# power_led_v4.net
KiCad netlist of a schematic drawn in EAGLE
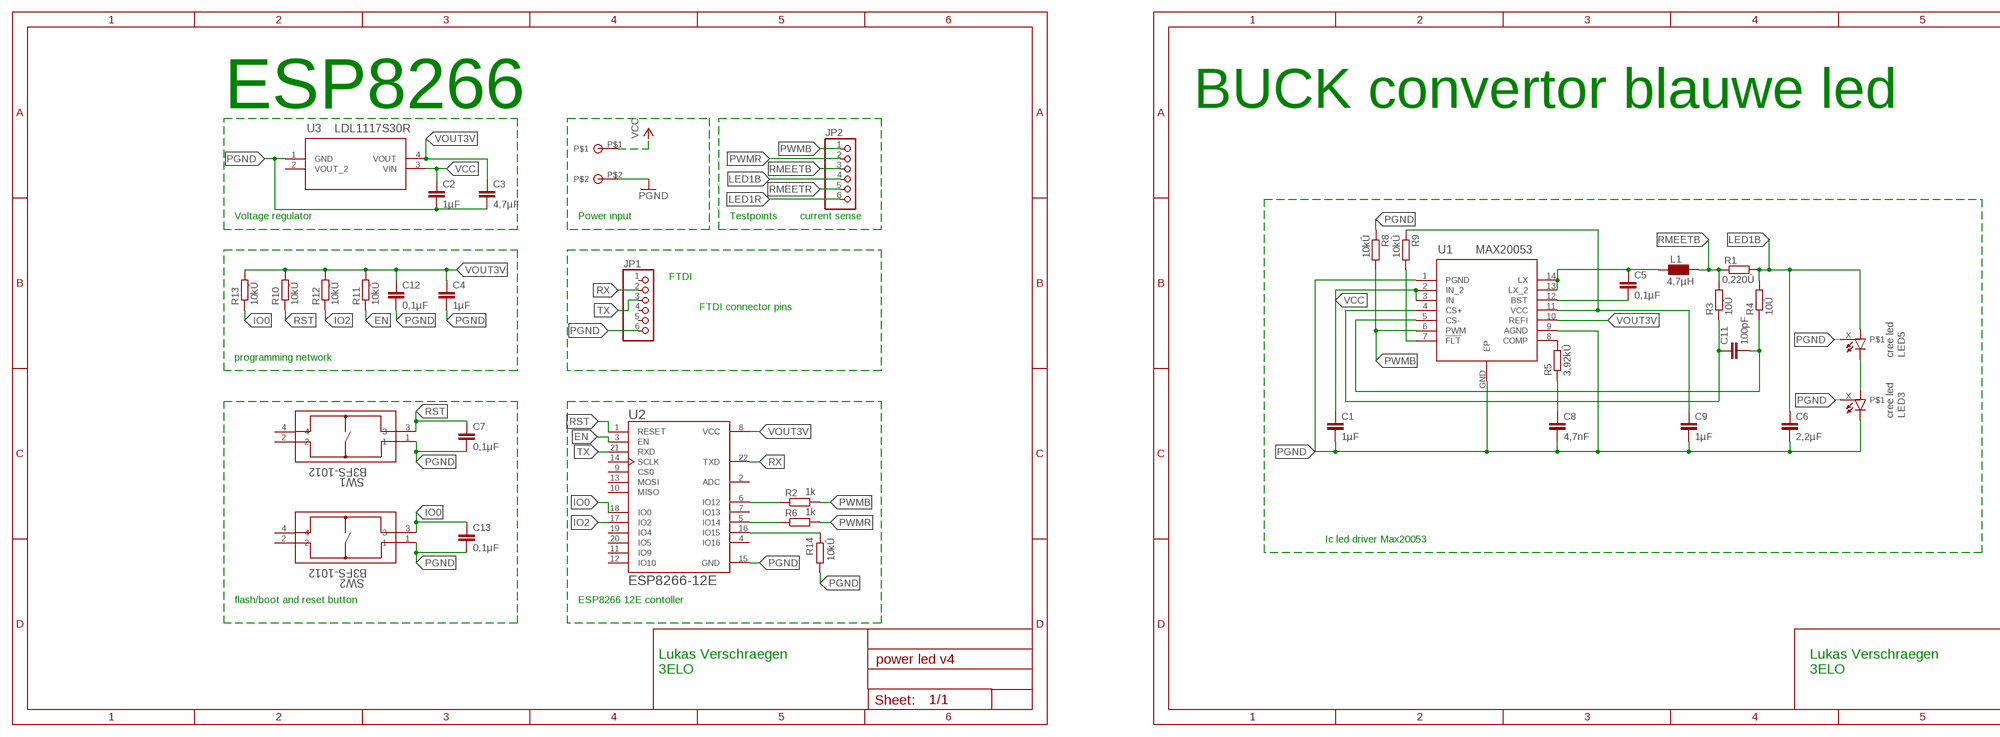
[diagram p0: schematic, sheet 1, part 1 of 2]
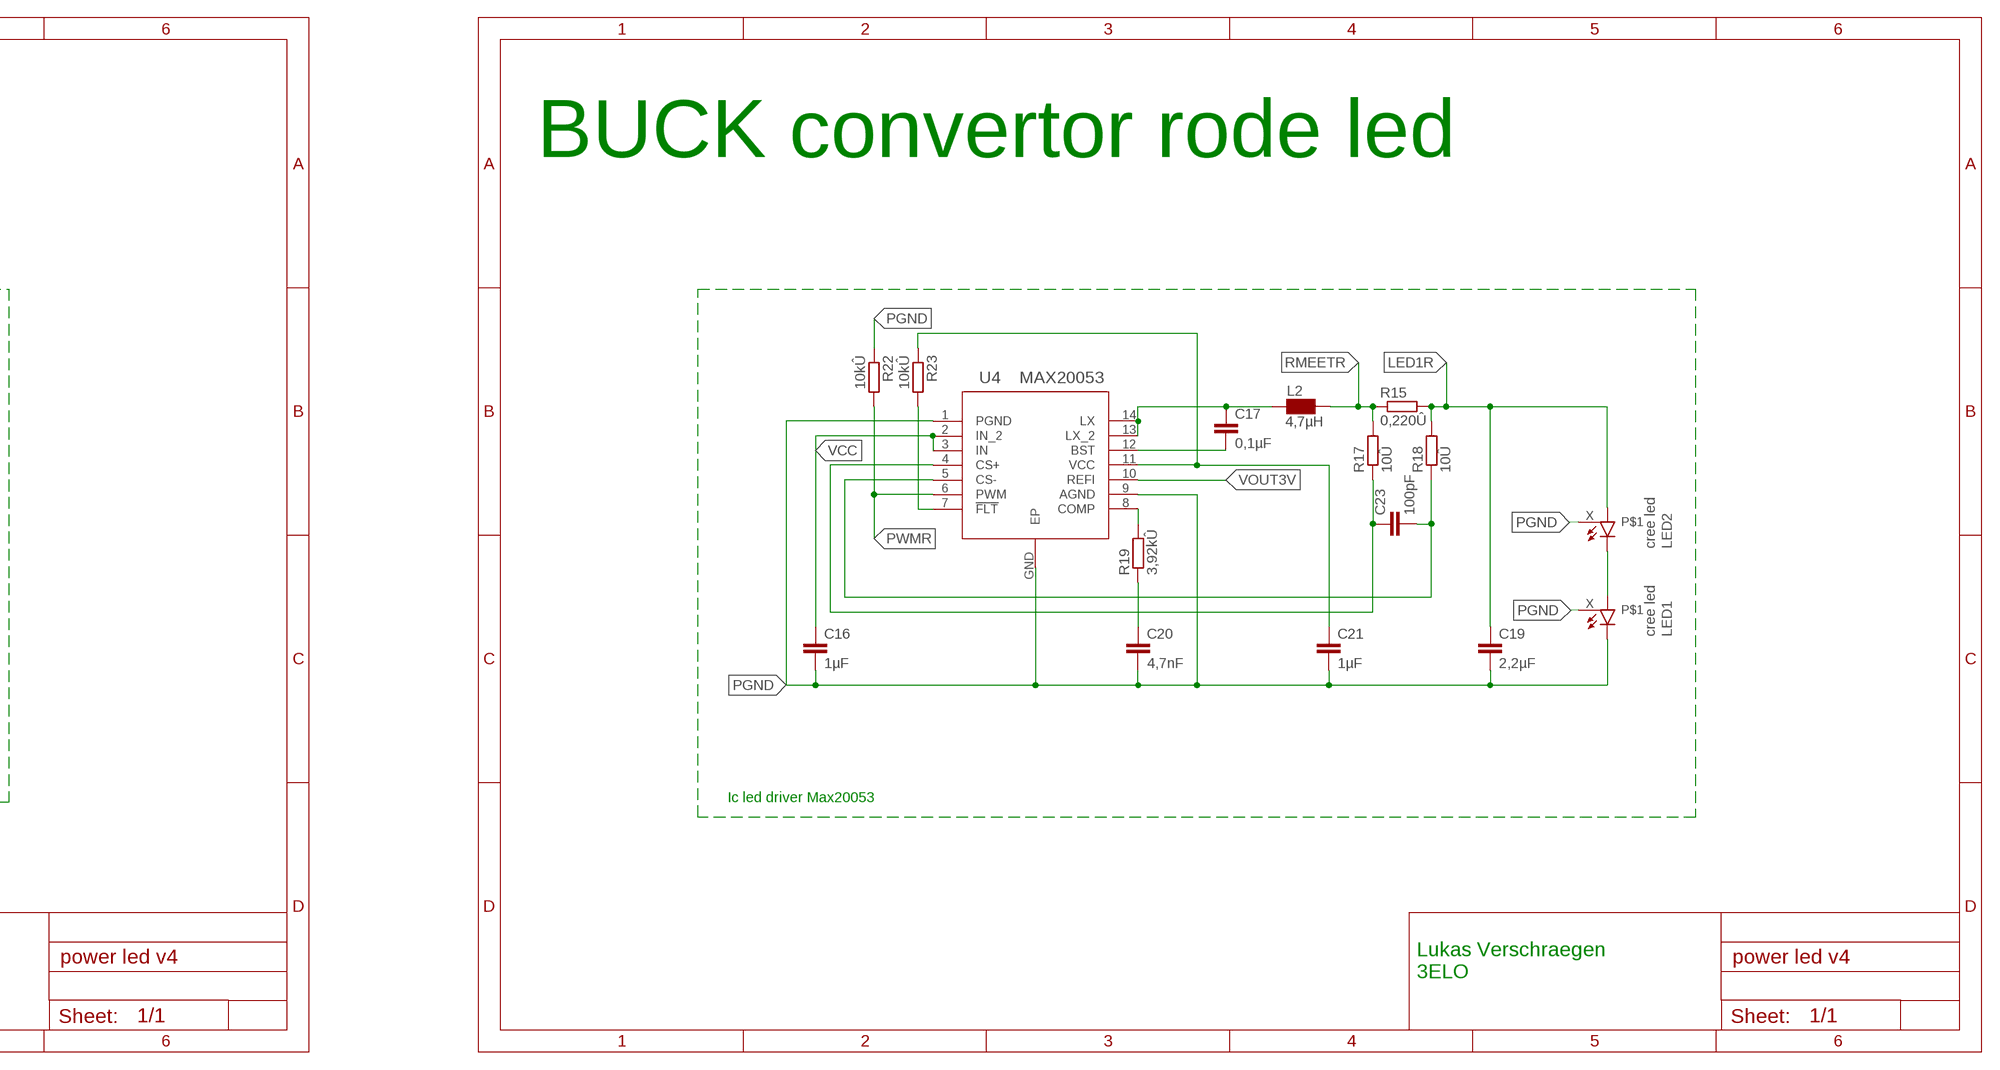
[diagram p1: schematic, sheet 1, part 2 of 2]

(export (version "E")
  (design (tool "Eeschema 10.0.6"))
  (components
    (comp (ref "C1")
      (value "1µF")
      (footprint "eagle-import:C1206")
      (libsource (lib "eagle-import") (part "C-EUC1206"))
    )
    (comp (ref "C2")
      (value "1µF")
      (footprint "eagle-import:C1206")
      (libsource (lib "eagle-import") (part "C-EUC1206"))
    )
    (comp (ref "C3")
      (value "4,7µF")
      (footprint "eagle-import:C1206")
      (libsource (lib "eagle-import") (part "C-EUC1206"))
    )
    (comp (ref "C4")
      (value "1µF")
      (footprint "eagle-import:C1206")
      (libsource (lib "eagle-import") (part "C-EUC1206"))
    )
    (comp (ref "C5")
      (value "0,1µF")
      (footprint "eagle-import:C1206")
      (libsource (lib "eagle-import") (part "C-EUC1206"))
    )
    (comp (ref "C6")
      (value "2,2µF")
      (footprint "eagle-import:C1206")
      (libsource (lib "eagle-import") (part "C-EUC1206"))
    )
    (comp (ref "C7")
      (value "0,1µF")
      (footprint "eagle-import:C1206")
      (libsource (lib "eagle-import") (part "C-EUC1206"))
    )
    (comp (ref "C8")
      (value "4,7nF")
      (footprint "eagle-import:C1206")
      (libsource (lib "eagle-import") (part "C-EUC1206"))
    )
    (comp (ref "C9")
      (value "1µF")
      (footprint "eagle-import:C1206")
      (libsource (lib "eagle-import") (part "C-EUC1206"))
    )
    (comp (ref "C11")
      (value "100pF")
      (footprint "eagle-import:C1206")
      (libsource (lib "eagle-import") (part "C-EUC1206"))
    )
    (comp (ref "C12")
      (value "0,1µF")
      (footprint "eagle-import:C1206")
      (libsource (lib "eagle-import") (part "C-EUC1206"))
    )
    (comp (ref "C13")
      (value "0,1µF")
      (footprint "eagle-import:C1206")
      (libsource (lib "eagle-import") (part "C-EUC1206"))
    )
    (comp (ref "C16")
      (value "1µF")
      (footprint "eagle-import:C1206")
      (libsource (lib "eagle-import") (part "C-EUC1206"))
    )
    (comp (ref "C17")
      (value "0,1µF")
      (footprint "eagle-import:C1206")
      (libsource (lib "eagle-import") (part "C-EUC1206"))
    )
    (comp (ref "C19")
      (value "2,2µF")
      (footprint "eagle-import:C1206")
      (libsource (lib "eagle-import") (part "C-EUC1206"))
    )
    (comp (ref "C20")
      (value "4,7nF")
      (footprint "eagle-import:C1206")
      (libsource (lib "eagle-import") (part "C-EUC1206"))
    )
    (comp (ref "C21")
      (value "1µF")
      (footprint "eagle-import:C1206")
      (libsource (lib "eagle-import") (part "C-EUC1206"))
    )
    (comp (ref "C23")
      (value "100pF")
      (footprint "eagle-import:C1206")
      (libsource (lib "eagle-import") (part "C-EUC1206"))
    )
    (comp (ref "JP1")
      (value "PINHD-1X6")
      (footprint "eagle-import:1X06")
      (libsource (lib "eagle-import") (part "PINHD-1X6"))
    )
    (comp (ref "JP2")
      (value "PINHD-1X6")
      (footprint "eagle-import:1X06")
      (libsource (lib "eagle-import") (part "PINHD-1X6"))
    )
    (comp (ref "L1")
      (value "4,7µH")
      (footprint "eagle-import:IND_7447789004_WRE-M")
      (fields
        (field (name "MANUFACTURER_PART_NUMBER") "7447789004")
        (field (name "COPYRIGHT") "Copyright (C) 2022 Ultra Librarian. All rights reserved.")
      )
      (libsource (lib "eagle-import") (part "7447789004IND_7447789004_WRE-M"))
    )
    (comp (ref "L2")
      (value "4,7µH")
      (footprint "eagle-import:IND_7447789004_WRE-M")
      (fields
        (field (name "MANUFACTURER_PART_NUMBER") "7447789004")
        (field (name "COPYRIGHT") "Copyright (C) 2022 Ultra Librarian. All rights reserved.")
      )
      (libsource (lib "eagle-import") (part "7447789004IND_7447789004_WRE-M"))
    )
    (comp (ref "LED1")
      (value "cree led")
      (footprint "eagle-import:CREE_XLAMP")
      (libsource (lib "eagle-import") (part "XPEWHT-01-0000-00BC2"))
    )
    (comp (ref "LED2")
      (value "cree led")
      (footprint "eagle-import:CREE_XLAMP")
      (libsource (lib "eagle-import") (part "XPEWHT-01-0000-00BC2"))
    )
    (comp (ref "LED3")
      (value "cree led")
      (footprint "eagle-import:CREE_XLAMP")
      (libsource (lib "eagle-import") (part "XPEWHT-01-0000-00BC2"))
    )
    (comp (ref "LED5")
      (value "cree led")
      (footprint "eagle-import:CREE_XLAMP")
      (libsource (lib "eagle-import") (part "XPEWHT-01-0000-00BC2"))
    )
    (comp (ref "R1")
      (value "0,220Û")
      (footprint "eagle-import:R1206")
      (libsource (lib "eagle-import") (part "R-EU_R1206"))
    )
    (comp (ref "R2")
      (value "1k")
      (footprint "eagle-import:R1206")
      (libsource (lib "eagle-import") (part "R-EU_R1206"))
    )
    (comp (ref "R3")
      (value "10Û")
      (footprint "eagle-import:R1206")
      (libsource (lib "eagle-import") (part "R-EU_R1206"))
    )
    (comp (ref "R4")
      (value "10Û")
      (footprint "eagle-import:R1206")
      (libsource (lib "eagle-import") (part "R-EU_R1206"))
    )
    (comp (ref "R5")
      (value "3,92kÛ")
      (footprint "eagle-import:R1206")
      (libsource (lib "eagle-import") (part "R-EU_R1206"))
    )
    (comp (ref "R6")
      (value "1k")
      (footprint "eagle-import:R1206")
      (libsource (lib "eagle-import") (part "R-EU_R1206"))
    )
    (comp (ref "R8")
      (value "10kÛ")
      (footprint "eagle-import:R1206")
      (libsource (lib "eagle-import") (part "R-EU_R1206"))
    )
    (comp (ref "R9")
      (value "10kÛ")
      (footprint "eagle-import:R1206")
      (libsource (lib "eagle-import") (part "R-EU_R1206"))
    )
    (comp (ref "R10")
      (value "10kÛ")
      (footprint "eagle-import:R1206")
      (libsource (lib "eagle-import") (part "R-EU_R1206"))
    )
    (comp (ref "R11")
      (value "10kÛ")
      (footprint "eagle-import:R1206")
      (libsource (lib "eagle-import") (part "R-EU_R1206"))
    )
    (comp (ref "R12")
      (value "10kÛ")
      (footprint "eagle-import:R1206")
      (libsource (lib "eagle-import") (part "R-EU_R1206"))
    )
    (comp (ref "R13")
      (value "10kÛ")
      (footprint "eagle-import:R1206")
      (libsource (lib "eagle-import") (part "R-EU_R1206"))
    )
    (comp (ref "R14")
      (value "10kÛ")
      (footprint "eagle-import:R1206")
      (libsource (lib "eagle-import") (part "R-EU_R1206"))
    )
    (comp (ref "R15")
      (value "0,220Û")
      (footprint "eagle-import:R1206")
      (libsource (lib "eagle-import") (part "R-EU_R1206"))
    )
    (comp (ref "R17")
      (value "10Û")
      (footprint "eagle-import:R1206")
      (libsource (lib "eagle-import") (part "R-EU_R1206"))
    )
    (comp (ref "R18")
      (value "10Û")
      (footprint "eagle-import:R1206")
      (libsource (lib "eagle-import") (part "R-EU_R1206"))
    )
    (comp (ref "R19")
      (value "3,92kÛ")
      (footprint "eagle-import:R1206")
      (libsource (lib "eagle-import") (part "R-EU_R1206"))
    )
    (comp (ref "R22")
      (value "10kÛ")
      (footprint "eagle-import:R1206")
      (libsource (lib "eagle-import") (part "R-EU_R1206"))
    )
    (comp (ref "R23")
      (value "10kÛ")
      (footprint "eagle-import:R1206")
      (libsource (lib "eagle-import") (part "R-EU_R1206"))
    )
    (comp (ref "SW1")
      (value "B3FS-1012")
      (footprint "eagle-import:SW_B3FS-1010_OMR")
      (fields (field (name "COPYRIGHT") "Copyright (C) 2018 Accelerated Designs. All rights reserved"))
      (libsource (lib "eagle-import") (part "B3FS-1012"))
    )
    (comp (ref "SW2")
      (value "B3FS-1012")
      (footprint "eagle-import:SW_B3FS-1010_OMR")
      (fields (field (name "COPYRIGHT") "Copyright (C) 2018 Accelerated Designs. All rights reserved"))
      (libsource (lib "eagle-import") (part "B3FS-1012"))
    )
    (comp (ref "U1")
      (value "MAX20053")
      (footprint "eagle-import:21-0108-E_14L_MXM-M")
      (fields
        (field (name "MANUFACTURER_PART_NUMBER") "MAX20053AUD/V+")
        (field (name "COPYRIGHT") "Copyright (C) 2022 Ultra Librarian. All rights reserved.")
      )
      (libsource (lib "eagle-import") (part "MAX20053AUD/V+21-0108-E_14L_MXM-M"))
    )
    (comp (ref "U2")
      (value "ESP8266-12E")
      (footprint "eagle-import:XCVR_ESP8266-12E_ESP-12E")
      (fields (field (name "MF") "AI-Thinker") (field (name "MP") "ESP8266-12E/ESP-12E"))
      (libsource (lib "eagle-import") (part "ESP8266-12E/ESP-12E"))
    )
    (comp (ref "U3")
      (value "LDL1117S30R")
      (footprint "eagle-import:SOT223_STM")
      (fields (field (name "COPYRIGHT") "Copyright (C) 2022 Ultra Librarian. All rights reserved."))
      (libsource (lib "eagle-import") (part "LDL1117S30R"))
    )
    (comp (ref "U4")
      (value "MAX20053")
      (footprint "eagle-import:21-0108-E_14L_MXM-M")
      (fields
        (field (name "MANUFACTURER_PART_NUMBER") "MAX20053AUD/V+")
        (field (name "COPYRIGHT") "Copyright (C) 2022 Ultra Librarian. All rights reserved.")
      )
      (libsource (lib "eagle-import") (part "MAX20053AUD/V+21-0108-E_14L_MXM-M"))
    )
    (comp (ref "X1")
      (value "TERMINA5MM")
      (footprint "eagle-import:TERMINAL5MM")
      (libsource (lib "eagle-import") (part "TERMINA5MM"))
    )
  )
  (nets
    (net (code "1") (name "EN") (class "Default")
      (node (ref "R11") (pin "1") (pinfunction "1_1") (pintype "passive"))
      (node (ref "U2") (pin "3") (pinfunction "EN_3") (pintype "input"))
    )
    (net (code "2") (name "IO0") (class "Default")
      (node (ref "C13") (pin "1") (pinfunction "1_1") (pintype "passive"))
      (node (ref "R13") (pin "1") (pinfunction "1_1") (pintype "passive"))
      (node (ref "SW2") (pin "3") (pinfunction "3_3") (pintype "passive"))
      (node (ref "U2") (pin "18") (pinfunction "IO0_18") (pintype "bidirectional"))
    )
    (net (code "3") (name "IO2") (class "Default")
      (node (ref "R12") (pin "1") (pinfunction "1_1") (pintype "passive"))
      (node (ref "U2") (pin "17") (pinfunction "IO2_17") (pintype "bidirectional"))
    )
    (net (code "4") (name "LED1B") (class "Default")
      (node (ref "C6") (pin "1") (pinfunction "1_1") (pintype "passive"))
      (node (ref "JP2") (pin "4") (pinfunction "4_4") (pintype "passive"))
      (node (ref "LED5") (pin "A") (pinfunction "A_A") (pintype "passive"))
      (node (ref "LED5") (pin "A@1") (pinfunction "A_A@1") (pintype "passive"))
      (node (ref "R1") (pin "2") (pinfunction "2_2") (pintype "passive"))
      (node (ref "R4") (pin "2") (pinfunction "2_2") (pintype "passive"))
    )
    (net (code "5") (name "LED1R") (class "Default")
      (node (ref "C19") (pin "1") (pinfunction "1_1") (pintype "passive"))
      (node (ref "JP2") (pin "6") (pinfunction "6_6") (pintype "passive"))
      (node (ref "LED2") (pin "A") (pinfunction "A_A") (pintype "passive"))
      (node (ref "LED2") (pin "A@1") (pinfunction "A_A@1") (pintype "passive"))
      (node (ref "R15") (pin "2") (pinfunction "2_2") (pintype "passive"))
      (node (ref "R18") (pin "2") (pinfunction "2_2") (pintype "passive"))
    )
    (net (code "6") (name "Net-(C8-Pad1)") (class "Default")
      (node (ref "C8") (pin "1") (pinfunction "1_1") (pintype "passive"))
      (node (ref "R5") (pin "1") (pinfunction "1_1") (pintype "passive"))
    )
    (net (code "7") (name "Net-(C20-Pad1)") (class "Default")
      (node (ref "C20") (pin "1") (pinfunction "1_1") (pintype "passive"))
      (node (ref "R19") (pin "1") (pinfunction "1_1") (pintype "passive"))
    )
    (net (code "8") (name "Net-(LED1-A-PadA@1)") (class "Default")
      (node (ref "LED1") (pin "A") (pinfunction "A_A") (pintype "passive"))
      (node (ref "LED1") (pin "A@1") (pinfunction "A_A@1") (pintype "passive"))
      (node (ref "LED2") (pin "C") (pinfunction "C_C") (pintype "passive"))
      (node (ref "LED2") (pin "C@1") (pinfunction "C_C@1") (pintype "passive"))
    )
    (net (code "9") (name "Net-(LED3-A-PadA@1)") (class "Default")
      (node (ref "LED3") (pin "A") (pinfunction "A_A") (pintype "passive"))
      (node (ref "LED3") (pin "A@1") (pinfunction "A_A@1") (pintype "passive"))
      (node (ref "LED5") (pin "C") (pinfunction "C_C") (pintype "passive"))
      (node (ref "LED5") (pin "C@1") (pinfunction "C_C@1") (pintype "passive"))
    )
    (net (code "10") (name "Net-(U1-BST)") (class "Default")
      (node (ref "C5") (pin "2") (pinfunction "2_2") (pintype "passive"))
      (node (ref "U1") (pin "12") (pinfunction "BST_12") (pintype "passive"))
    )
    (net (code "11") (name "Net-(U1-COMP)") (class "Default")
      (node (ref "R5") (pin "2") (pinfunction "2_2") (pintype "passive"))
      (node (ref "U1") (pin "8") (pinfunction "COMP_8") (pintype "output"))
    )
    (net (code "12") (name "Net-(U1-CS+)") (class "Default")
      (node (ref "C11") (pin "1") (pinfunction "1_1") (pintype "passive"))
      (node (ref "R3") (pin "1") (pinfunction "1_1") (pintype "passive"))
      (node (ref "U1") (pin "4") (pinfunction "CS+_4") (pintype "input"))
    )
    (net (code "13") (name "Net-(U1-CS-)") (class "Default")
      (node (ref "C11") (pin "2") (pinfunction "2_2") (pintype "passive"))
      (node (ref "R4") (pin "1") (pinfunction "1_1") (pintype "passive"))
      (node (ref "U1") (pin "5") (pinfunction "CS-_5") (pintype "input"))
    )
    (net (code "14") (name "Net-(U1-LX)") (class "Default")
      (node (ref "C5") (pin "1") (pinfunction "1_1") (pintype "passive"))
      (node (ref "L1") (pin "2") (pinfunction "2_2") (pintype "passive"))
      (node (ref "U1") (pin "13") (pinfunction "LX_2_13") (pintype "output"))
      (node (ref "U1") (pin "14") (pinfunction "LX_14") (pintype "output"))
    )
    (net (code "15") (name "Net-(U1-VCC)") (class "Default")
      (node (ref "C9") (pin "1") (pinfunction "1_1") (pintype "passive"))
      (node (ref "R9") (pin "1") (pinfunction "1_1") (pintype "passive"))
      (node (ref "U1") (pin "11") (pinfunction "VCC_11") (pintype "power_in"))
    )
    (net (code "16") (name "Net-(U1-~{FLT})") (class "Default")
      (node (ref "R9") (pin "2") (pinfunction "2_2") (pintype "passive"))
      (node (ref "U1") (pin "7") (pinfunction "~{FLT}_7") (pintype "output"))
    )
    (net (code "17") (name "Net-(U2-IO12)") (class "Default")
      (node (ref "R2") (pin "1") (pinfunction "1_1") (pintype "passive"))
      (node (ref "U2") (pin "6") (pinfunction "IO12_6") (pintype "bidirectional"))
    )
    (net (code "18") (name "Net-(U2-IO14)") (class "Default")
      (node (ref "R6") (pin "1") (pinfunction "1_1") (pintype "passive"))
      (node (ref "U2") (pin "5") (pinfunction "IO14_5") (pintype "bidirectional"))
    )
    (net (code "19") (name "Net-(U2-IO15)") (class "Default")
      (node (ref "R14") (pin "1") (pinfunction "1_1") (pintype "passive"))
      (node (ref "U2") (pin "16") (pinfunction "IO15_16") (pintype "bidirectional"))
    )
    (net (code "20") (name "Net-(U4-BST)") (class "Default")
      (node (ref "C17") (pin "2") (pinfunction "2_2") (pintype "passive"))
      (node (ref "U4") (pin "12") (pinfunction "BST_12") (pintype "passive"))
    )
    (net (code "21") (name "Net-(U4-COMP)") (class "Default")
      (node (ref "R19") (pin "2") (pinfunction "2_2") (pintype "passive"))
      (node (ref "U4") (pin "8") (pinfunction "COMP_8") (pintype "output"))
    )
    (net (code "22") (name "Net-(U4-CS+)") (class "Default")
      (node (ref "C23") (pin "1") (pinfunction "1_1") (pintype "passive"))
      (node (ref "R17") (pin "1") (pinfunction "1_1") (pintype "passive"))
      (node (ref "U4") (pin "4") (pinfunction "CS+_4") (pintype "input"))
    )
    (net (code "23") (name "Net-(U4-CS-)") (class "Default")
      (node (ref "C23") (pin "2") (pinfunction "2_2") (pintype "passive"))
      (node (ref "R18") (pin "1") (pinfunction "1_1") (pintype "passive"))
      (node (ref "U4") (pin "5") (pinfunction "CS-_5") (pintype "input"))
    )
    (net (code "24") (name "Net-(U4-LX)") (class "Default")
      (node (ref "C17") (pin "1") (pinfunction "1_1") (pintype "passive"))
      (node (ref "L2") (pin "2") (pinfunction "2_2") (pintype "passive"))
      (node (ref "U4") (pin "13") (pinfunction "LX_2_13") (pintype "output"))
      (node (ref "U4") (pin "14") (pinfunction "LX_14") (pintype "output"))
    )
    (net (code "25") (name "Net-(U4-VCC)") (class "Default")
      (node (ref "C21") (pin "1") (pinfunction "1_1") (pintype "passive"))
      (node (ref "R23") (pin "1") (pinfunction "1_1") (pintype "passive"))
      (node (ref "U4") (pin "11") (pinfunction "VCC_11") (pintype "power_in"))
    )
    (net (code "26") (name "Net-(U4-~{FLT})") (class "Default")
      (node (ref "R23") (pin "2") (pinfunction "2_2") (pintype "passive"))
      (node (ref "U4") (pin "7") (pinfunction "~{FLT}_7") (pintype "output"))
    )
    (net (code "27") (name "PGND") (class "Default")
      (node (ref "C1") (pin "2") (pinfunction "2_2") (pintype "passive"))
      (node (ref "C12") (pin "2") (pinfunction "2_2") (pintype "passive"))
      (node (ref "C13") (pin "2") (pinfunction "2_2") (pintype "passive"))
      (node (ref "C16") (pin "2") (pinfunction "2_2") (pintype "passive"))
      (node (ref "C19") (pin "2") (pinfunction "2_2") (pintype "passive"))
      (node (ref "C2") (pin "2") (pinfunction "2_2") (pintype "passive"))
      (node (ref "C20") (pin "2") (pinfunction "2_2") (pintype "passive"))
      (node (ref "C21") (pin "2") (pinfunction "2_2") (pintype "passive"))
      (node (ref "C3") (pin "2") (pinfunction "2_2") (pintype "passive"))
      (node (ref "C4") (pin "2") (pinfunction "2_2") (pintype "passive"))
      (node (ref "C6") (pin "2") (pinfunction "2_2") (pintype "passive"))
      (node (ref "C7") (pin "2") (pinfunction "2_2") (pintype "passive"))
      (node (ref "C8") (pin "2") (pinfunction "2_2") (pintype "passive"))
      (node (ref "C9") (pin "2") (pinfunction "2_2") (pintype "passive"))
      (node (ref "JP1") (pin "6") (pinfunction "6_6") (pintype "passive"))
      (node (ref "LED1") (pin "C") (pinfunction "C_C") (pintype "passive"))
      (node (ref "LED1") (pin "C@1") (pinfunction "C_C@1") (pintype "passive"))
      (node (ref "LED1") (pin "X") (pinfunction "P$1_X") (pintype "bidirectional"))
      (node (ref "LED2") (pin "X") (pinfunction "P$1_X") (pintype "bidirectional"))
      (node (ref "LED3") (pin "C") (pinfunction "C_C") (pintype "passive"))
      (node (ref "LED3") (pin "C@1") (pinfunction "C_C@1") (pintype "passive"))
      (node (ref "LED3") (pin "X") (pinfunction "P$1_X") (pintype "bidirectional"))
      (node (ref "LED5") (pin "X") (pinfunction "P$1_X") (pintype "bidirectional"))
      (node (ref "R14") (pin "2") (pinfunction "2_2") (pintype "passive"))
      (node (ref "R22") (pin "1") (pinfunction "1_1") (pintype "passive"))
      (node (ref "R8") (pin "1") (pinfunction "1_1") (pintype "passive"))
      (node (ref "SW1") (pin "1") (pinfunction "1_1") (pintype "passive"))
      (node (ref "SW2") (pin "1") (pinfunction "1_1") (pintype "passive"))
      (node (ref "U1") (pin "1") (pinfunction "PGND_1") (pintype "power_in"))
      (node (ref "U1") (pin "9") (pinfunction "AGND_9") (pintype "power_in"))
      (node (ref "U1") (pin "GND") (pinfunction "EP_GND") (pintype "bidirectional"))
      (node (ref "U2") (pin "15") (pinfunction "GND_15") (pintype "power_in"))
      (node (ref "U3") (pin "1") (pinfunction "GND_1") (pintype "passive"))
      (node (ref "U4") (pin "1") (pinfunction "PGND_1") (pintype "power_in"))
      (node (ref "U4") (pin "9") (pinfunction "AGND_9") (pintype "power_in"))
      (node (ref "U4") (pin "GND") (pinfunction "EP_GND") (pintype "bidirectional"))
      (node (ref "X1") (pin "P$2") (pinfunction "P$2_P$2") (pintype "input"))
    )
    (net (code "28") (name "PWMB") (class "Default")
      (node (ref "JP2") (pin "1") (pinfunction "1_1") (pintype "passive"))
      (node (ref "R2") (pin "2") (pinfunction "2_2") (pintype "passive"))
      (node (ref "R8") (pin "2") (pinfunction "2_2") (pintype "passive"))
      (node (ref "U1") (pin "6") (pinfunction "PWM_6") (pintype "input"))
    )
    (net (code "29") (name "PWMR") (class "Default")
      (node (ref "JP2") (pin "2") (pinfunction "2_2") (pintype "passive"))
      (node (ref "R22") (pin "2") (pinfunction "2_2") (pintype "passive"))
      (node (ref "R6") (pin "2") (pinfunction "2_2") (pintype "passive"))
      (node (ref "U4") (pin "6") (pinfunction "PWM_6") (pintype "input"))
    )
    (net (code "30") (name "RMEETB") (class "Default")
      (node (ref "JP2") (pin "3") (pinfunction "3_3") (pintype "passive"))
      (node (ref "L1") (pin "1") (pinfunction "1_1") (pintype "passive"))
      (node (ref "R1") (pin "1") (pinfunction "1_1") (pintype "passive"))
      (node (ref "R3") (pin "2") (pinfunction "2_2") (pintype "passive"))
    )
    (net (code "31") (name "RMEETR") (class "Default")
      (node (ref "JP2") (pin "5") (pinfunction "5_5") (pintype "passive"))
      (node (ref "L2") (pin "1") (pinfunction "1_1") (pintype "passive"))
      (node (ref "R15") (pin "1") (pinfunction "1_1") (pintype "passive"))
      (node (ref "R17") (pin "2") (pinfunction "2_2") (pintype "passive"))
    )
    (net (code "32") (name "RST") (class "Default")
      (node (ref "C7") (pin "1") (pinfunction "1_1") (pintype "passive"))
      (node (ref "R10") (pin "1") (pinfunction "1_1") (pintype "passive"))
      (node (ref "SW1") (pin "3") (pinfunction "3_3") (pintype "passive"))
      (node (ref "U2") (pin "1") (pinfunction "RESET_1") (pintype "input"))
    )
    (net (code "33") (name "RX") (class "Default")
      (node (ref "JP1") (pin "2") (pinfunction "2_2") (pintype "passive"))
      (node (ref "U2") (pin "22") (pinfunction "TXD_22") (pintype "output"))
    )
    (net (code "34") (name "TX") (class "Default")
      (node (ref "JP1") (pin "3") (pinfunction "3_3") (pintype "passive"))
      (node (ref "U2") (pin "21") (pinfunction "RXD_21") (pintype "input"))
    )
    (net (code "35") (name "VCC") (class "Default")
      (node (ref "C1") (pin "1") (pinfunction "1_1") (pintype "passive"))
      (node (ref "C16") (pin "1") (pinfunction "1_1") (pintype "passive"))
      (node (ref "C2") (pin "1") (pinfunction "1_1") (pintype "passive"))
      (node (ref "U1") (pin "2") (pinfunction "IN_2_2") (pintype "input"))
      (node (ref "U1") (pin "3") (pinfunction "IN_3") (pintype "input"))
      (node (ref "U3") (pin "3") (pinfunction "VIN_3") (pintype "power_in"))
      (node (ref "U4") (pin "2") (pinfunction "IN_2_2") (pintype "input"))
      (node (ref "U4") (pin "3") (pinfunction "IN_3") (pintype "input"))
      (node (ref "X1") (pin "P$1") (pinfunction "P$1_P$1") (pintype "input"))
    )
    (net (code "36") (name "VOUT3V") (class "Default")
      (node (ref "C12") (pin "1") (pinfunction "1_1") (pintype "passive"))
      (node (ref "C3") (pin "1") (pinfunction "1_1") (pintype "passive"))
      (node (ref "C4") (pin "1") (pinfunction "1_1") (pintype "passive"))
      (node (ref "R10") (pin "2") (pinfunction "2_2") (pintype "passive"))
      (node (ref "R11") (pin "2") (pinfunction "2_2") (pintype "passive"))
      (node (ref "R12") (pin "2") (pinfunction "2_2") (pintype "passive"))
      (node (ref "R13") (pin "2") (pinfunction "2_2") (pintype "passive"))
      (node (ref "U1") (pin "10") (pinfunction "REFI_10") (pintype "input"))
      (node (ref "U2") (pin "8") (pinfunction "VCC_8") (pintype "power_in"))
      (node (ref "U3") (pin "4") (pinfunction "VOUT_4") (pintype "output"))
      (node (ref "U4") (pin "10") (pinfunction "REFI_10") (pintype "input"))
    )
    (net (code "37") (name "unconnected-(JP1-Pad1)") (class "Default")
      (node (ref "JP1") (pin "1") (pinfunction "1_1") (pintype "passive"))
    )
    (net (code "38") (name "unconnected-(JP1-Pad4)") (class "Default")
      (node (ref "JP1") (pin "4") (pinfunction "4_4") (pintype "passive"))
    )
    (net (code "39") (name "unconnected-(JP1-Pad5)") (class "Default")
      (node (ref "JP1") (pin "5") (pinfunction "5_5") (pintype "passive"))
    )
    (net (code "40") (name "unconnected-(SW1-Pad2)") (class "Default")
      (node (ref "SW1") (pin "2") (pinfunction "2_2") (pintype "passive"))
    )
    (net (code "41") (name "unconnected-(SW1-Pad4)") (class "Default")
      (node (ref "SW1") (pin "4") (pinfunction "4_4") (pintype "passive"))
    )
    (net (code "42") (name "unconnected-(SW2-Pad2)") (class "Default")
      (node (ref "SW2") (pin "2") (pinfunction "2_2") (pintype "passive"))
    )
    (net (code "43") (name "unconnected-(SW2-Pad4)") (class "Default")
      (node (ref "SW2") (pin "4") (pinfunction "4_4") (pintype "passive"))
    )
    (net (code "44") (name "unconnected-(U2-ADC-Pad2)") (class "Default")
      (node (ref "U2") (pin "2") (pinfunction "ADC_2") (pintype "passive"))
    )
    (net (code "45") (name "unconnected-(U2-CS0-Pad9)") (class "Default")
      (node (ref "U2") (pin "9") (pinfunction "CS0_9") (pintype "input"))
    )
    (net (code "46") (name "unconnected-(U2-IO4-Pad19)") (class "Default")
      (node (ref "U2") (pin "19") (pinfunction "IO4_19") (pintype "bidirectional"))
    )
    (net (code "47") (name "unconnected-(U2-IO5-Pad20)") (class "Default")
      (node (ref "U2") (pin "20") (pinfunction "IO5_20") (pintype "bidirectional"))
    )
    (net (code "48") (name "unconnected-(U2-IO9-Pad11)") (class "Default")
      (node (ref "U2") (pin "11") (pinfunction "IO9_11") (pintype "bidirectional"))
    )
    (net (code "49") (name "unconnected-(U2-IO10-Pad12)") (class "Default")
      (node (ref "U2") (pin "12") (pinfunction "IO10_12") (pintype "bidirectional"))
    )
    (net (code "50") (name "unconnected-(U2-IO13-Pad7)") (class "Default")
      (node (ref "U2") (pin "7") (pinfunction "IO13_7") (pintype "bidirectional"))
    )
    (net (code "51") (name "unconnected-(U2-IO16-Pad4)") (class "Default")
      (node (ref "U2") (pin "4") (pinfunction "IO16_4") (pintype "bidirectional"))
    )
    (net (code "52") (name "unconnected-(U2-MISO-Pad10)") (class "Default")
      (node (ref "U2") (pin "10") (pinfunction "MISO_10") (pintype "bidirectional"))
    )
    (net (code "53") (name "unconnected-(U2-MOSI-Pad13)") (class "Default")
      (node (ref "U2") (pin "13") (pinfunction "MOSI_13") (pintype "bidirectional"))
    )
    (net (code "54") (name "unconnected-(U2-SCLK-Pad14)") (class "Default")
      (node (ref "U2") (pin "14") (pinfunction "SCLK_14") (pintype "input"))
    )
    (net (code "55") (name "unconnected-(U3-VOUT_2-Pad2)") (class "Default")
      (node (ref "U3") (pin "2") (pinfunction "VOUT_2_2") (pintype "output"))
    )
  )
)
